# mini-store-selector.net
KiCad netlist of a schematic drawn in EAGLE
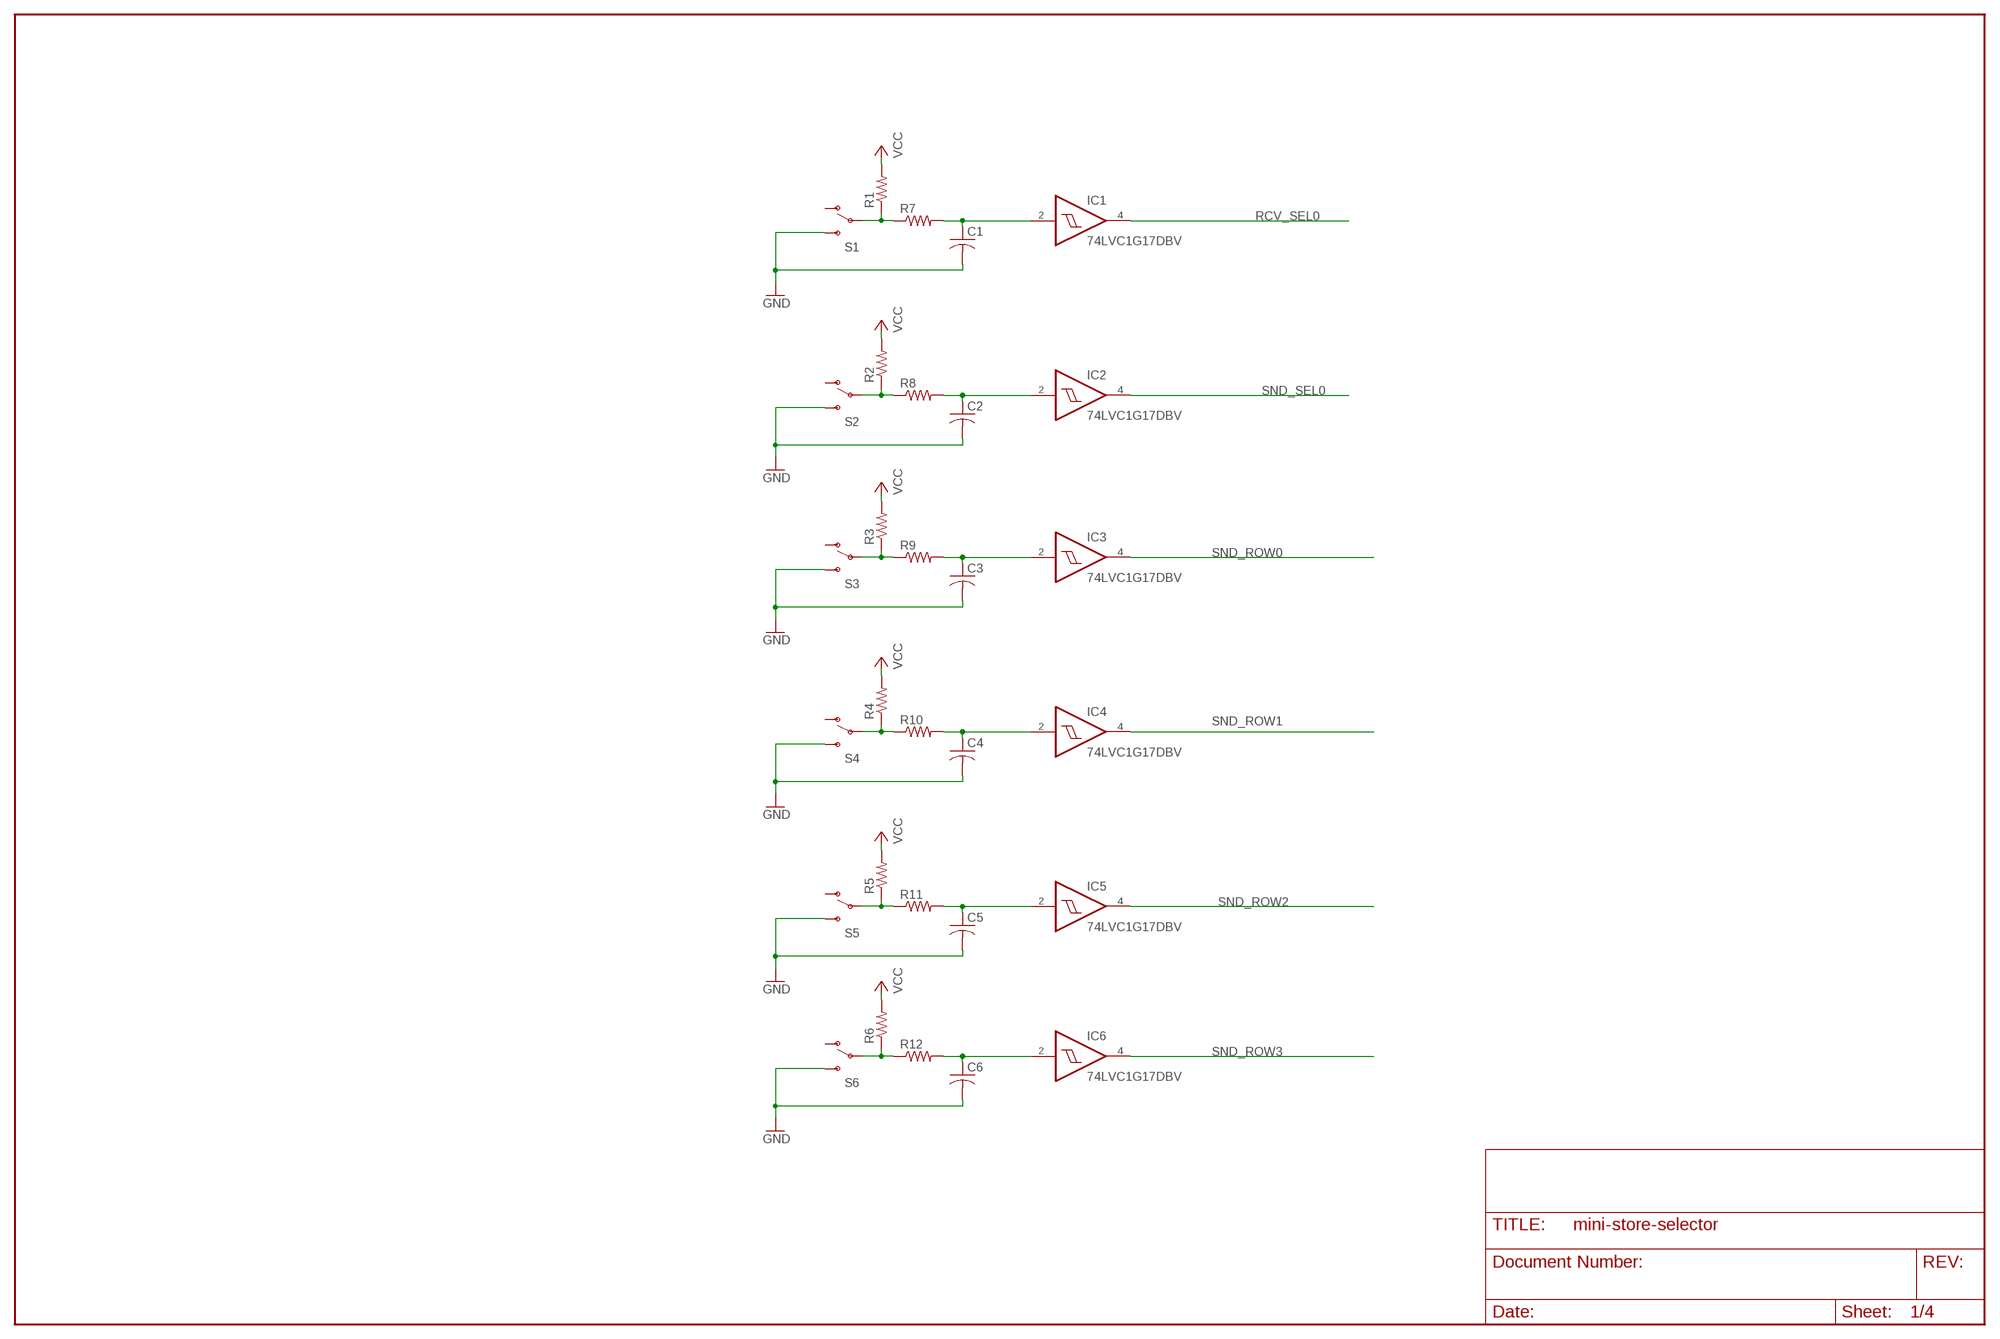
[diagram p0: schematic, sheet 1]
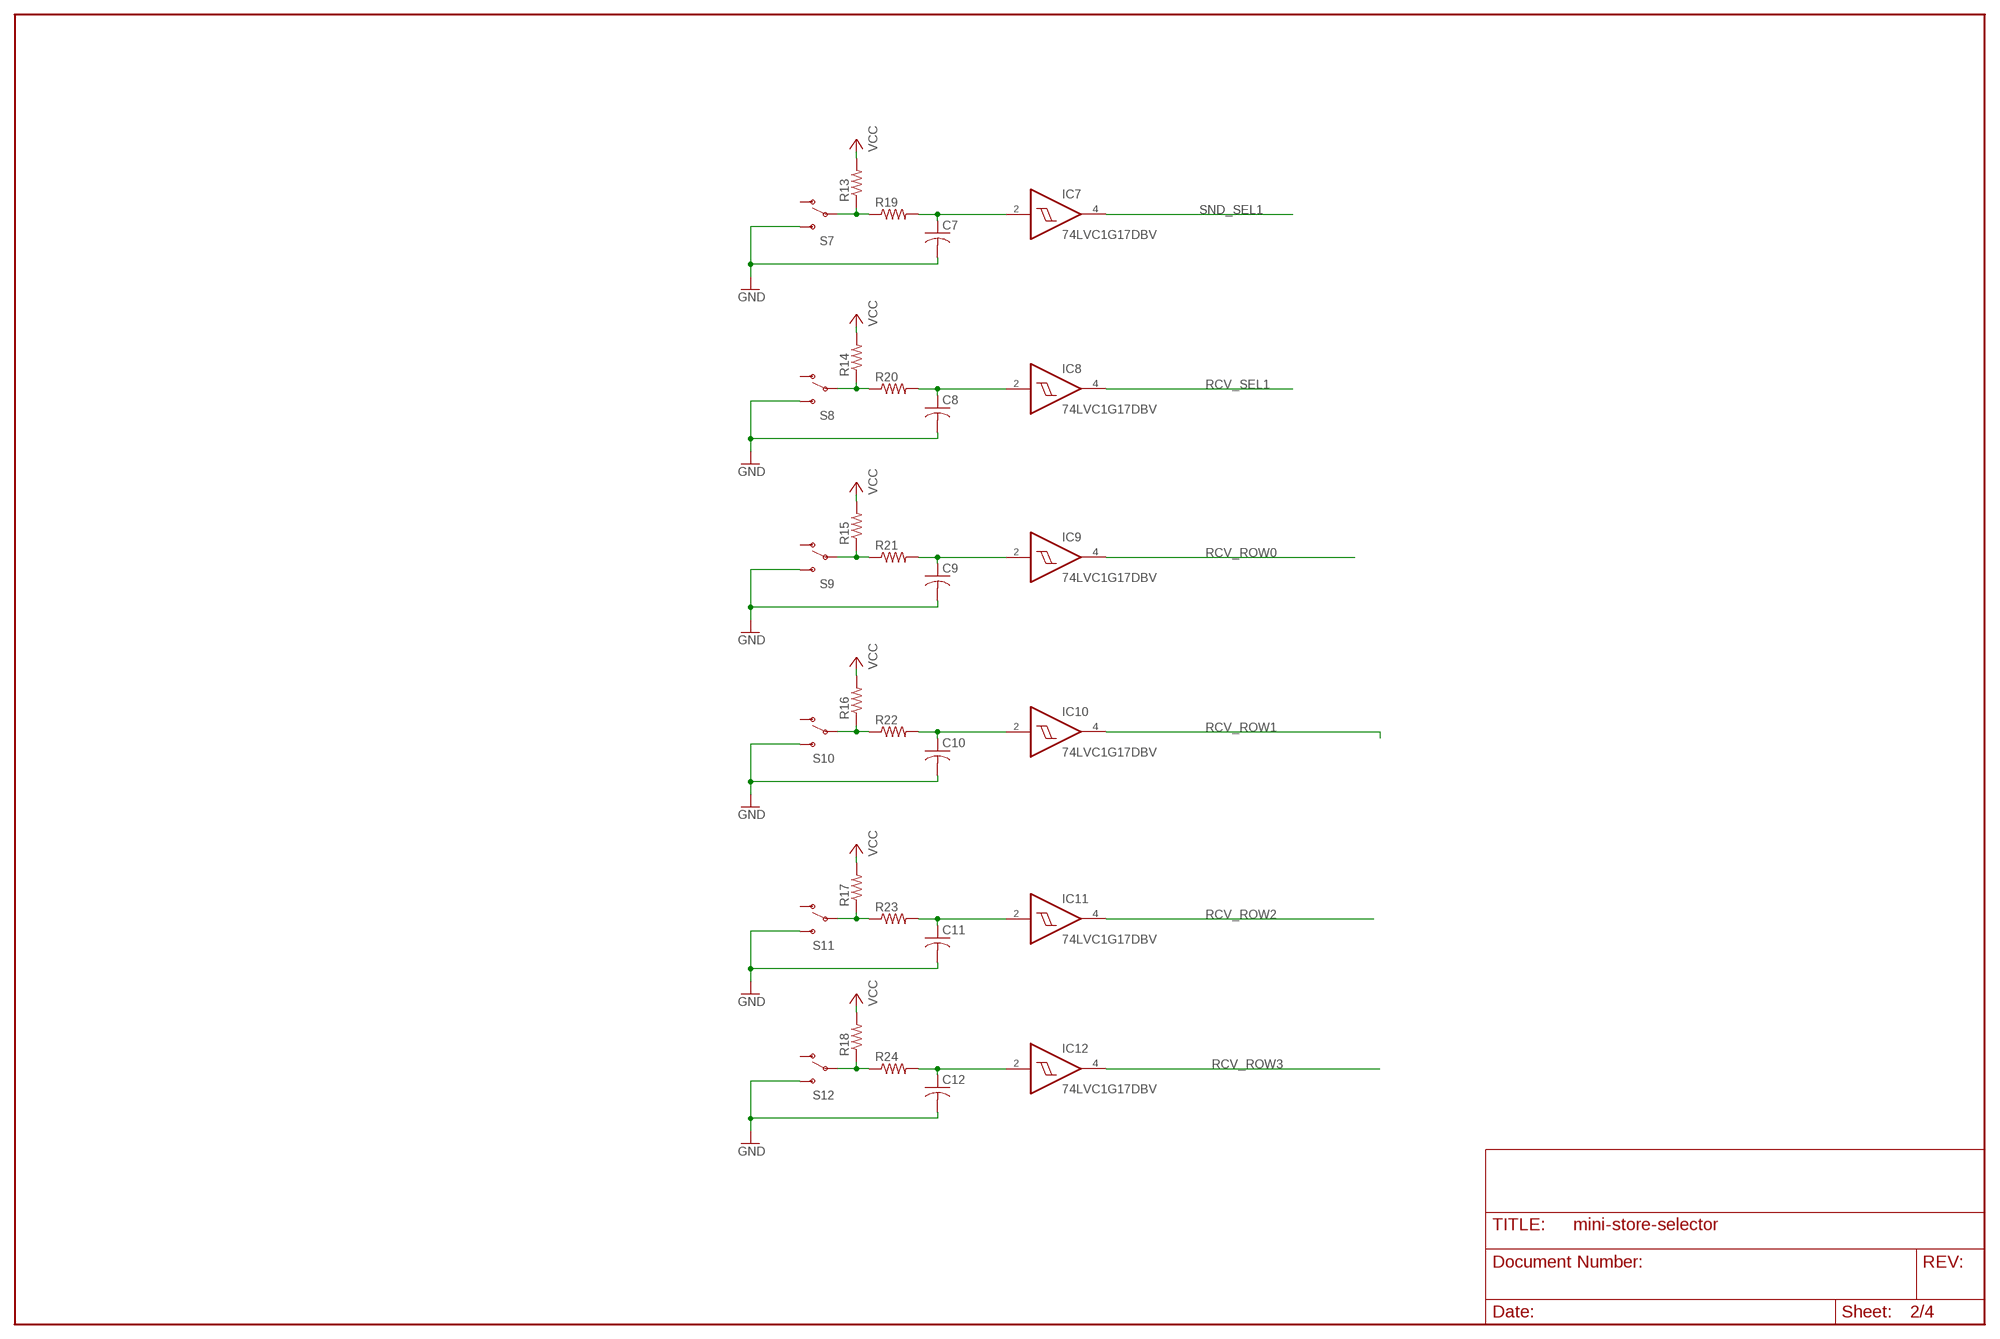
[diagram p1: schematic, sheet 2]
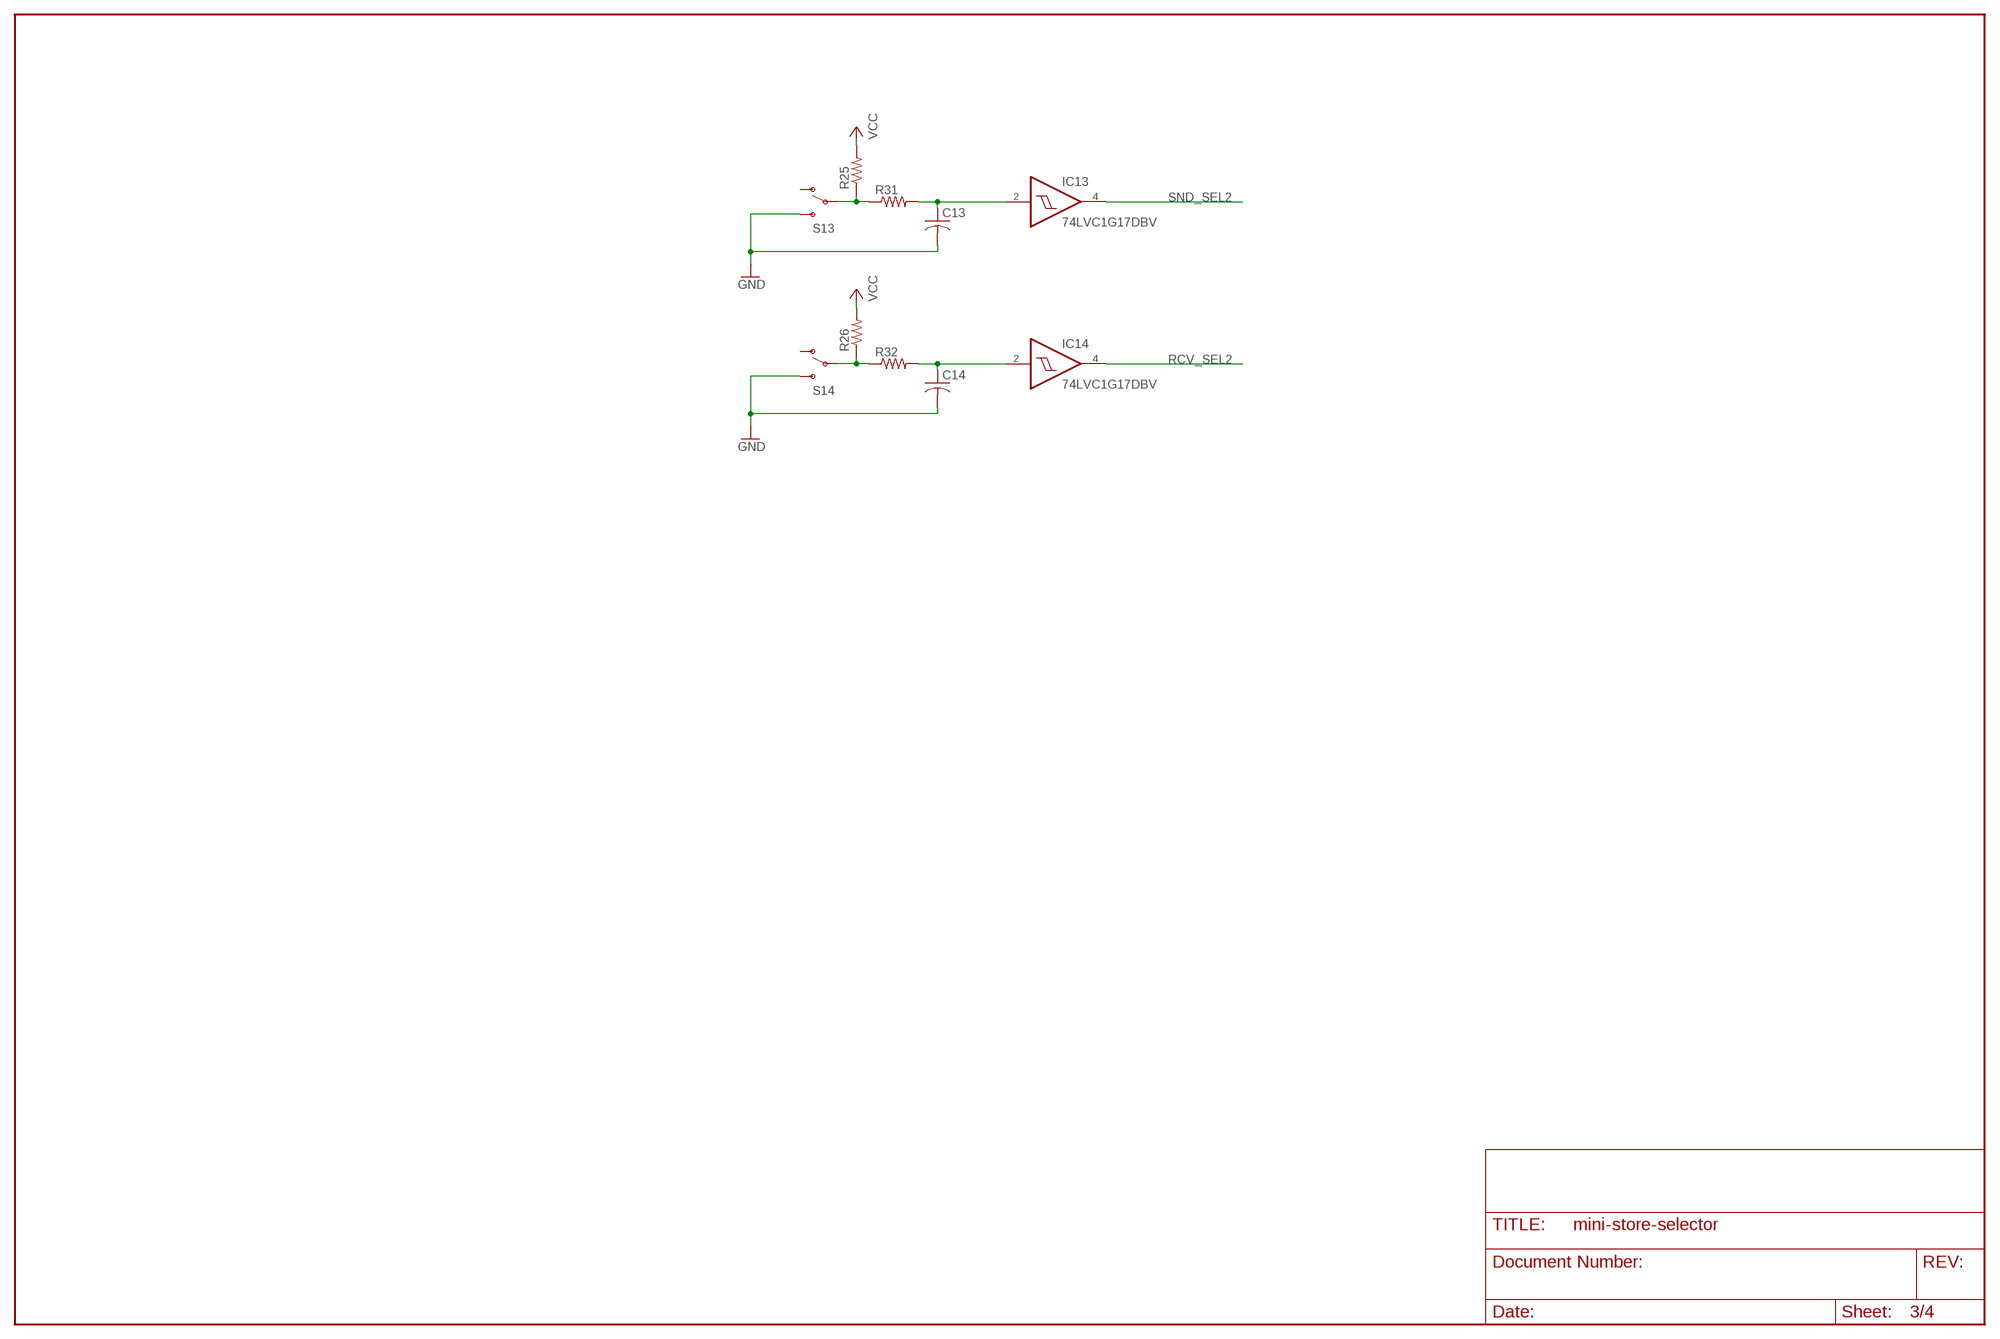
[diagram p2: schematic, sheet 3]
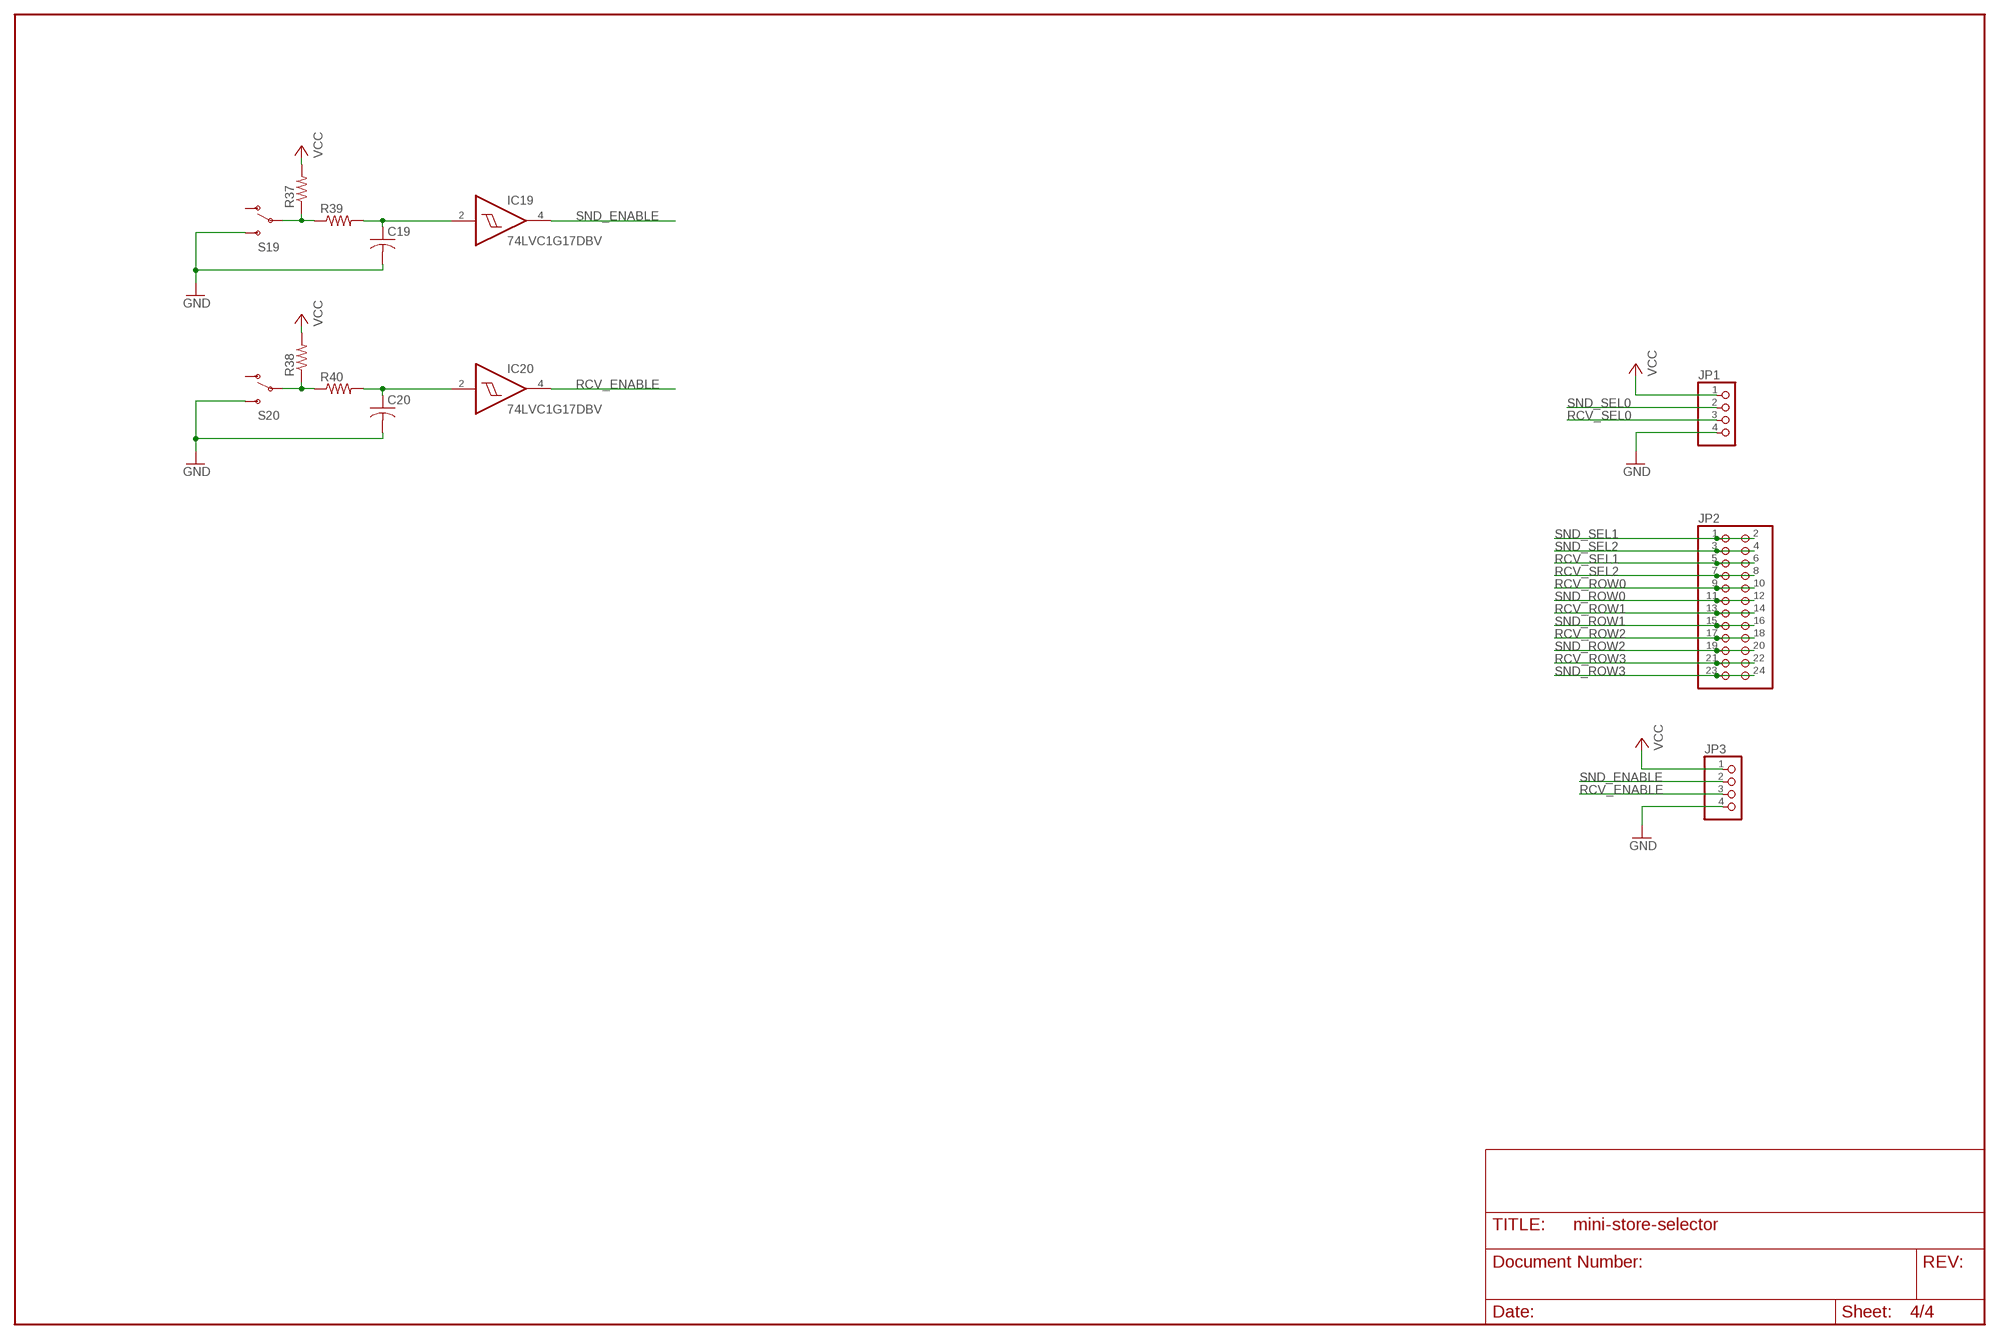
[diagram p3: schematic, sheet 4]

(export (version "E")
  (design (tool "Eeschema 10.0.6"))
  (components
    (comp (ref "C19")
      (value "C-USC0805")
      (footprint "eagle-import:C0805")
      (libsource (lib "eagle-import") (part "C-USC0805"))
    )
    (comp (ref "C20")
      (value "C-USC0805")
      (footprint "eagle-import:C0805")
      (libsource (lib "eagle-import") (part "C-USC0805"))
    )
    (comp (ref "IC19")
      (value "74LVC1G17DBV")
      (footprint "eagle-import:SOT23-5")
      (libsource (lib "eagle-import") (part "741G17DBVLVC"))
    )
    (comp (ref "IC20")
      (value "74LVC1G17DBV")
      (footprint "eagle-import:SOT23-5")
      (libsource (lib "eagle-import") (part "741G17DBVLVC"))
    )
    (comp (ref "JP1")
      (value "PINHD-1X4")
      (footprint "eagle-import:1X04")
      (libsource (lib "eagle-import") (part "PINHD-1X4"))
    )
    (comp (ref "JP2")
      (value "PINHD-2X12")
      (footprint "eagle-import:2X12")
      (libsource (lib "eagle-import") (part "PINHD-2X12"))
    )
    (comp (ref "JP3")
      (value "PINHD-1X4")
      (footprint "eagle-import:1X04")
      (libsource (lib "eagle-import") (part "PINHD-1X4"))
    )
    (comp (ref "R37")
      (value "R-US_R0805")
      (footprint "eagle-import:R0805")
      (libsource (lib "eagle-import") (part "R-US_R0805"))
    )
    (comp (ref "R38")
      (value "R-US_R0805")
      (footprint "eagle-import:R0805")
      (libsource (lib "eagle-import") (part "R-US_R0805"))
    )
    (comp (ref "R39")
      (value "R-US_R0805")
      (footprint "eagle-import:R0805")
      (libsource (lib "eagle-import") (part "R-US_R0805"))
    )
    (comp (ref "R40")
      (value "R-US_R0805")
      (footprint "eagle-import:R0805")
      (libsource (lib "eagle-import") (part "R-US_R0805"))
    )
    (comp (ref "S19")
      (value "SWITCH-SPDTPTH")
      (footprint "eagle-import:SWITCH-SPDT")
      (libsource (lib "eagle-import") (part "SWITCH-SPDTPTH"))
    )
    (comp (ref "S20")
      (value "SWITCH-SPDTPTH")
      (footprint "eagle-import:SWITCH-SPDT")
      (libsource (lib "eagle-import") (part "SWITCH-SPDTPTH"))
    )
    (comp (ref "C7")
      (value "C-USC0805")
      (footprint "eagle-import:C0805")
      (libsource (lib "eagle-import") (part "C-USC0805"))
    )
    (comp (ref "C8")
      (value "C-USC0805")
      (footprint "eagle-import:C0805")
      (libsource (lib "eagle-import") (part "C-USC0805"))
    )
    (comp (ref "C9")
      (value "C-USC0805")
      (footprint "eagle-import:C0805")
      (libsource (lib "eagle-import") (part "C-USC0805"))
    )
    (comp (ref "C10")
      (value "C-USC0805")
      (footprint "eagle-import:C0805")
      (libsource (lib "eagle-import") (part "C-USC0805"))
    )
    (comp (ref "C11")
      (value "C-USC0805")
      (footprint "eagle-import:C0805")
      (libsource (lib "eagle-import") (part "C-USC0805"))
    )
    (comp (ref "C12")
      (value "C-USC0805")
      (footprint "eagle-import:C0805")
      (libsource (lib "eagle-import") (part "C-USC0805"))
    )
    (comp (ref "IC7")
      (value "74LVC1G17DBV")
      (footprint "eagle-import:SOT23-5")
      (libsource (lib "eagle-import") (part "741G17DBVLVC"))
    )
    (comp (ref "IC8")
      (value "74LVC1G17DBV")
      (footprint "eagle-import:SOT23-5")
      (libsource (lib "eagle-import") (part "741G17DBVLVC"))
    )
    (comp (ref "IC9")
      (value "74LVC1G17DBV")
      (footprint "eagle-import:SOT23-5")
      (libsource (lib "eagle-import") (part "741G17DBVLVC"))
    )
    (comp (ref "IC10")
      (value "74LVC1G17DBV")
      (footprint "eagle-import:SOT23-5")
      (libsource (lib "eagle-import") (part "741G17DBVLVC"))
    )
    (comp (ref "IC11")
      (value "74LVC1G17DBV")
      (footprint "eagle-import:SOT23-5")
      (libsource (lib "eagle-import") (part "741G17DBVLVC"))
    )
    (comp (ref "IC12")
      (value "74LVC1G17DBV")
      (footprint "eagle-import:SOT23-5")
      (libsource (lib "eagle-import") (part "741G17DBVLVC"))
    )
    (comp (ref "R13")
      (value "R-US_R0805")
      (footprint "eagle-import:R0805")
      (libsource (lib "eagle-import") (part "R-US_R0805"))
    )
    (comp (ref "R14")
      (value "R-US_R0805")
      (footprint "eagle-import:R0805")
      (libsource (lib "eagle-import") (part "R-US_R0805"))
    )
    (comp (ref "R15")
      (value "R-US_R0805")
      (footprint "eagle-import:R0805")
      (libsource (lib "eagle-import") (part "R-US_R0805"))
    )
    (comp (ref "R16")
      (value "R-US_R0805")
      (footprint "eagle-import:R0805")
      (libsource (lib "eagle-import") (part "R-US_R0805"))
    )
    (comp (ref "R17")
      (value "R-US_R0805")
      (footprint "eagle-import:R0805")
      (libsource (lib "eagle-import") (part "R-US_R0805"))
    )
    (comp (ref "R18")
      (value "R-US_R0805")
      (footprint "eagle-import:R0805")
      (libsource (lib "eagle-import") (part "R-US_R0805"))
    )
    (comp (ref "R19")
      (value "R-US_R0805")
      (footprint "eagle-import:R0805")
      (libsource (lib "eagle-import") (part "R-US_R0805"))
    )
    (comp (ref "R20")
      (value "R-US_R0805")
      (footprint "eagle-import:R0805")
      (libsource (lib "eagle-import") (part "R-US_R0805"))
    )
    (comp (ref "R21")
      (value "R-US_R0805")
      (footprint "eagle-import:R0805")
      (libsource (lib "eagle-import") (part "R-US_R0805"))
    )
    (comp (ref "R22")
      (value "R-US_R0805")
      (footprint "eagle-import:R0805")
      (libsource (lib "eagle-import") (part "R-US_R0805"))
    )
    (comp (ref "R23")
      (value "R-US_R0805")
      (footprint "eagle-import:R0805")
      (libsource (lib "eagle-import") (part "R-US_R0805"))
    )
    (comp (ref "R24")
      (value "R-US_R0805")
      (footprint "eagle-import:R0805")
      (libsource (lib "eagle-import") (part "R-US_R0805"))
    )
    (comp (ref "S7")
      (value "SWITCH-SPDTPTH")
      (footprint "eagle-import:SWITCH-SPDT")
      (libsource (lib "eagle-import") (part "SWITCH-SPDTPTH"))
    )
    (comp (ref "S8")
      (value "SWITCH-SPDTPTH")
      (footprint "eagle-import:SWITCH-SPDT")
      (libsource (lib "eagle-import") (part "SWITCH-SPDTPTH"))
    )
    (comp (ref "S9")
      (value "SWITCH-SPDTPTH")
      (footprint "eagle-import:SWITCH-SPDT")
      (libsource (lib "eagle-import") (part "SWITCH-SPDTPTH"))
    )
    (comp (ref "S10")
      (value "SWITCH-SPDTPTH")
      (footprint "eagle-import:SWITCH-SPDT")
      (libsource (lib "eagle-import") (part "SWITCH-SPDTPTH"))
    )
    (comp (ref "S11")
      (value "SWITCH-SPDTPTH")
      (footprint "eagle-import:SWITCH-SPDT")
      (libsource (lib "eagle-import") (part "SWITCH-SPDTPTH"))
    )
    (comp (ref "S12")
      (value "SWITCH-SPDTPTH")
      (footprint "eagle-import:SWITCH-SPDT")
      (libsource (lib "eagle-import") (part "SWITCH-SPDTPTH"))
    )
    (comp (ref "C1")
      (value "C-USC0805")
      (footprint "eagle-import:C0805")
      (libsource (lib "eagle-import") (part "C-USC0805"))
    )
    (comp (ref "C2")
      (value "C-USC0805")
      (footprint "eagle-import:C0805")
      (libsource (lib "eagle-import") (part "C-USC0805"))
    )
    (comp (ref "C3")
      (value "C-USC0805")
      (footprint "eagle-import:C0805")
      (libsource (lib "eagle-import") (part "C-USC0805"))
    )
    (comp (ref "C4")
      (value "C-USC0805")
      (footprint "eagle-import:C0805")
      (libsource (lib "eagle-import") (part "C-USC0805"))
    )
    (comp (ref "C5")
      (value "C-USC0805")
      (footprint "eagle-import:C0805")
      (libsource (lib "eagle-import") (part "C-USC0805"))
    )
    (comp (ref "C6")
      (value "C-USC0805")
      (footprint "eagle-import:C0805")
      (libsource (lib "eagle-import") (part "C-USC0805"))
    )
    (comp (ref "IC1")
      (value "74LVC1G17DBV")
      (footprint "eagle-import:SOT23-5")
      (libsource (lib "eagle-import") (part "741G17DBVLVC"))
    )
    (comp (ref "IC2")
      (value "74LVC1G17DBV")
      (footprint "eagle-import:SOT23-5")
      (libsource (lib "eagle-import") (part "741G17DBVLVC"))
    )
    (comp (ref "IC3")
      (value "74LVC1G17DBV")
      (footprint "eagle-import:SOT23-5")
      (libsource (lib "eagle-import") (part "741G17DBVLVC"))
    )
    (comp (ref "IC4")
      (value "74LVC1G17DBV")
      (footprint "eagle-import:SOT23-5")
      (libsource (lib "eagle-import") (part "741G17DBVLVC"))
    )
    (comp (ref "IC5")
      (value "74LVC1G17DBV")
      (footprint "eagle-import:SOT23-5")
      (libsource (lib "eagle-import") (part "741G17DBVLVC"))
    )
    (comp (ref "IC6")
      (value "74LVC1G17DBV")
      (footprint "eagle-import:SOT23-5")
      (libsource (lib "eagle-import") (part "741G17DBVLVC"))
    )
    (comp (ref "R1")
      (value "R-US_R0805")
      (footprint "eagle-import:R0805")
      (libsource (lib "eagle-import") (part "R-US_R0805"))
    )
    (comp (ref "R2")
      (value "R-US_R0805")
      (footprint "eagle-import:R0805")
      (libsource (lib "eagle-import") (part "R-US_R0805"))
    )
    (comp (ref "R3")
      (value "R-US_R0805")
      (footprint "eagle-import:R0805")
      (libsource (lib "eagle-import") (part "R-US_R0805"))
    )
    (comp (ref "R4")
      (value "R-US_R0805")
      (footprint "eagle-import:R0805")
      (libsource (lib "eagle-import") (part "R-US_R0805"))
    )
    (comp (ref "R5")
      (value "R-US_R0805")
      (footprint "eagle-import:R0805")
      (libsource (lib "eagle-import") (part "R-US_R0805"))
    )
    (comp (ref "R6")
      (value "R-US_R0805")
      (footprint "eagle-import:R0805")
      (libsource (lib "eagle-import") (part "R-US_R0805"))
    )
    (comp (ref "R7")
      (value "R-US_R0805")
      (footprint "eagle-import:R0805")
      (libsource (lib "eagle-import") (part "R-US_R0805"))
    )
    (comp (ref "R8")
      (value "R-US_R0805")
      (footprint "eagle-import:R0805")
      (libsource (lib "eagle-import") (part "R-US_R0805"))
    )
    (comp (ref "R9")
      (value "R-US_R0805")
      (footprint "eagle-import:R0805")
      (libsource (lib "eagle-import") (part "R-US_R0805"))
    )
    (comp (ref "R10")
      (value "R-US_R0805")
      (footprint "eagle-import:R0805")
      (libsource (lib "eagle-import") (part "R-US_R0805"))
    )
    (comp (ref "R11")
      (value "R-US_R0805")
      (footprint "eagle-import:R0805")
      (libsource (lib "eagle-import") (part "R-US_R0805"))
    )
    (comp (ref "R12")
      (value "R-US_R0805")
      (footprint "eagle-import:R0805")
      (libsource (lib "eagle-import") (part "R-US_R0805"))
    )
    (comp (ref "S1")
      (value "SWITCH-SPDTPTH")
      (footprint "eagle-import:SWITCH-SPDT")
      (libsource (lib "eagle-import") (part "SWITCH-SPDTPTH"))
    )
    (comp (ref "S2")
      (value "SWITCH-SPDTPTH")
      (footprint "eagle-import:SWITCH-SPDT")
      (libsource (lib "eagle-import") (part "SWITCH-SPDTPTH"))
    )
    (comp (ref "S3")
      (value "SWITCH-SPDTPTH")
      (footprint "eagle-import:SWITCH-SPDT")
      (libsource (lib "eagle-import") (part "SWITCH-SPDTPTH"))
    )
    (comp (ref "S4")
      (value "SWITCH-SPDTPTH")
      (footprint "eagle-import:SWITCH-SPDT")
      (libsource (lib "eagle-import") (part "SWITCH-SPDTPTH"))
    )
    (comp (ref "S5")
      (value "SWITCH-SPDTPTH")
      (footprint "eagle-import:SWITCH-SPDT")
      (libsource (lib "eagle-import") (part "SWITCH-SPDTPTH"))
    )
    (comp (ref "S6")
      (value "SWITCH-SPDTPTH")
      (footprint "eagle-import:SWITCH-SPDT")
      (libsource (lib "eagle-import") (part "SWITCH-SPDTPTH"))
    )
    (comp (ref "C13")
      (value "C-USC0805")
      (footprint "eagle-import:C0805")
      (libsource (lib "eagle-import") (part "C-USC0805"))
    )
    (comp (ref "C14")
      (value "C-USC0805")
      (footprint "eagle-import:C0805")
      (libsource (lib "eagle-import") (part "C-USC0805"))
    )
    (comp (ref "IC13")
      (value "74LVC1G17DBV")
      (footprint "eagle-import:SOT23-5")
      (libsource (lib "eagle-import") (part "741G17DBVLVC"))
    )
    (comp (ref "IC14")
      (value "74LVC1G17DBV")
      (footprint "eagle-import:SOT23-5")
      (libsource (lib "eagle-import") (part "741G17DBVLVC"))
    )
    (comp (ref "R25")
      (value "R-US_R0805")
      (footprint "eagle-import:R0805")
      (libsource (lib "eagle-import") (part "R-US_R0805"))
    )
    (comp (ref "R26")
      (value "R-US_R0805")
      (footprint "eagle-import:R0805")
      (libsource (lib "eagle-import") (part "R-US_R0805"))
    )
    (comp (ref "R31")
      (value "R-US_R0805")
      (footprint "eagle-import:R0805")
      (libsource (lib "eagle-import") (part "R-US_R0805"))
    )
    (comp (ref "R32")
      (value "R-US_R0805")
      (footprint "eagle-import:R0805")
      (libsource (lib "eagle-import") (part "R-US_R0805"))
    )
    (comp (ref "S13")
      (value "SWITCH-SPDTPTH")
      (footprint "eagle-import:SWITCH-SPDT")
      (libsource (lib "eagle-import") (part "SWITCH-SPDTPTH"))
    )
    (comp (ref "S14")
      (value "SWITCH-SPDTPTH")
      (footprint "eagle-import:SWITCH-SPDT")
      (libsource (lib "eagle-import") (part "SWITCH-SPDTPTH"))
    )
  )
  (nets
    (net (code "1") (name "GND") (class "Default")
      (node (ref "C1") (pin "2") (pinfunction "2_2") (pintype "passive"))
      (node (ref "C10") (pin "2") (pinfunction "2_2") (pintype "passive"))
      (node (ref "C11") (pin "2") (pinfunction "2_2") (pintype "passive"))
      (node (ref "C12") (pin "2") (pinfunction "2_2") (pintype "passive"))
      (node (ref "C13") (pin "2") (pinfunction "2_2") (pintype "passive"))
      (node (ref "C14") (pin "2") (pinfunction "2_2") (pintype "passive"))
      (node (ref "C19") (pin "2") (pinfunction "2_2") (pintype "passive"))
      (node (ref "C2") (pin "2") (pinfunction "2_2") (pintype "passive"))
      (node (ref "C20") (pin "2") (pinfunction "2_2") (pintype "passive"))
      (node (ref "C3") (pin "2") (pinfunction "2_2") (pintype "passive"))
      (node (ref "C4") (pin "2") (pinfunction "2_2") (pintype "passive"))
      (node (ref "C5") (pin "2") (pinfunction "2_2") (pintype "passive"))
      (node (ref "C6") (pin "2") (pinfunction "2_2") (pintype "passive"))
      (node (ref "C7") (pin "2") (pinfunction "2_2") (pintype "passive"))
      (node (ref "C8") (pin "2") (pinfunction "2_2") (pintype "passive"))
      (node (ref "C9") (pin "2") (pinfunction "2_2") (pintype "passive"))
      (node (ref "JP1") (pin "4") (pinfunction "4_4") (pintype "passive"))
      (node (ref "JP3") (pin "4") (pinfunction "4_4") (pintype "passive"))
      (node (ref "S1") (pin "3") (pinfunction "S_3") (pintype "passive"))
      (node (ref "S10") (pin "3") (pinfunction "S_3") (pintype "passive"))
      (node (ref "S11") (pin "3") (pinfunction "S_3") (pintype "passive"))
      (node (ref "S12") (pin "3") (pinfunction "S_3") (pintype "passive"))
      (node (ref "S13") (pin "3") (pinfunction "S_3") (pintype "passive"))
      (node (ref "S14") (pin "3") (pinfunction "S_3") (pintype "passive"))
      (node (ref "S19") (pin "3") (pinfunction "S_3") (pintype "passive"))
      (node (ref "S2") (pin "3") (pinfunction "S_3") (pintype "passive"))
      (node (ref "S20") (pin "3") (pinfunction "S_3") (pintype "passive"))
      (node (ref "S3") (pin "3") (pinfunction "S_3") (pintype "passive"))
      (node (ref "S4") (pin "3") (pinfunction "S_3") (pintype "passive"))
      (node (ref "S5") (pin "3") (pinfunction "S_3") (pintype "passive"))
      (node (ref "S6") (pin "3") (pinfunction "S_3") (pintype "passive"))
      (node (ref "S7") (pin "3") (pinfunction "S_3") (pintype "passive"))
      (node (ref "S8") (pin "3") (pinfunction "S_3") (pintype "passive"))
      (node (ref "S9") (pin "3") (pinfunction "S_3") (pintype "passive"))
    )
    (net (code "2") (name "Net-(IC1A-I)") (class "Default")
      (node (ref "C1") (pin "1") (pinfunction "1_1") (pintype "passive"))
      (node (ref "IC1") (pin "2") (pinfunction "I_2") (pintype "input"))
      (node (ref "R7") (pin "2") (pinfunction "2_2") (pintype "passive"))
    )
    (net (code "3") (name "Net-(IC2A-I)") (class "Default")
      (node (ref "C2") (pin "1") (pinfunction "1_1") (pintype "passive"))
      (node (ref "IC2") (pin "2") (pinfunction "I_2") (pintype "input"))
      (node (ref "R8") (pin "2") (pinfunction "2_2") (pintype "passive"))
    )
    (net (code "4") (name "Net-(IC3A-I)") (class "Default")
      (node (ref "C3") (pin "1") (pinfunction "1_1") (pintype "passive"))
      (node (ref "IC3") (pin "2") (pinfunction "I_2") (pintype "input"))
      (node (ref "R9") (pin "2") (pinfunction "2_2") (pintype "passive"))
    )
    (net (code "5") (name "Net-(IC4A-I)") (class "Default")
      (node (ref "C4") (pin "1") (pinfunction "1_1") (pintype "passive"))
      (node (ref "IC4") (pin "2") (pinfunction "I_2") (pintype "input"))
      (node (ref "R10") (pin "2") (pinfunction "2_2") (pintype "passive"))
    )
    (net (code "6") (name "Net-(IC5A-I)") (class "Default")
      (node (ref "C5") (pin "1") (pinfunction "1_1") (pintype "passive"))
      (node (ref "IC5") (pin "2") (pinfunction "I_2") (pintype "input"))
      (node (ref "R11") (pin "2") (pinfunction "2_2") (pintype "passive"))
    )
    (net (code "7") (name "Net-(IC6A-I)") (class "Default")
      (node (ref "C6") (pin "1") (pinfunction "1_1") (pintype "passive"))
      (node (ref "IC6") (pin "2") (pinfunction "I_2") (pintype "input"))
      (node (ref "R12") (pin "2") (pinfunction "2_2") (pintype "passive"))
    )
    (net (code "8") (name "Net-(IC7A-I)") (class "Default")
      (node (ref "C7") (pin "1") (pinfunction "1_1") (pintype "passive"))
      (node (ref "IC7") (pin "2") (pinfunction "I_2") (pintype "input"))
      (node (ref "R19") (pin "2") (pinfunction "2_2") (pintype "passive"))
    )
    (net (code "9") (name "Net-(IC8A-I)") (class "Default")
      (node (ref "C8") (pin "1") (pinfunction "1_1") (pintype "passive"))
      (node (ref "IC8") (pin "2") (pinfunction "I_2") (pintype "input"))
      (node (ref "R20") (pin "2") (pinfunction "2_2") (pintype "passive"))
    )
    (net (code "10") (name "Net-(IC9A-I)") (class "Default")
      (node (ref "C9") (pin "1") (pinfunction "1_1") (pintype "passive"))
      (node (ref "IC9") (pin "2") (pinfunction "I_2") (pintype "input"))
      (node (ref "R21") (pin "2") (pinfunction "2_2") (pintype "passive"))
    )
    (net (code "11") (name "Net-(IC10A-I)") (class "Default")
      (node (ref "C10") (pin "1") (pinfunction "1_1") (pintype "passive"))
      (node (ref "IC10") (pin "2") (pinfunction "I_2") (pintype "input"))
      (node (ref "R22") (pin "2") (pinfunction "2_2") (pintype "passive"))
    )
    (net (code "12") (name "Net-(IC11A-I)") (class "Default")
      (node (ref "C11") (pin "1") (pinfunction "1_1") (pintype "passive"))
      (node (ref "IC11") (pin "2") (pinfunction "I_2") (pintype "input"))
      (node (ref "R23") (pin "2") (pinfunction "2_2") (pintype "passive"))
    )
    (net (code "13") (name "Net-(IC12A-I)") (class "Default")
      (node (ref "C12") (pin "1") (pinfunction "1_1") (pintype "passive"))
      (node (ref "IC12") (pin "2") (pinfunction "I_2") (pintype "input"))
      (node (ref "R24") (pin "2") (pinfunction "2_2") (pintype "passive"))
    )
    (net (code "14") (name "Net-(IC13A-I)") (class "Default")
      (node (ref "C13") (pin "1") (pinfunction "1_1") (pintype "passive"))
      (node (ref "IC13") (pin "2") (pinfunction "I_2") (pintype "input"))
      (node (ref "R31") (pin "2") (pinfunction "2_2") (pintype "passive"))
    )
    (net (code "15") (name "Net-(IC14A-I)") (class "Default")
      (node (ref "C14") (pin "1") (pinfunction "1_1") (pintype "passive"))
      (node (ref "IC14") (pin "2") (pinfunction "I_2") (pintype "input"))
      (node (ref "R32") (pin "2") (pinfunction "2_2") (pintype "passive"))
    )
    (net (code "16") (name "Net-(IC19A-I)") (class "Default")
      (node (ref "C19") (pin "1") (pinfunction "1_1") (pintype "passive"))
      (node (ref "IC19") (pin "2") (pinfunction "I_2") (pintype "input"))
      (node (ref "R39") (pin "2") (pinfunction "2_2") (pintype "passive"))
    )
    (net (code "17") (name "Net-(IC20A-I)") (class "Default")
      (node (ref "C20") (pin "1") (pinfunction "1_1") (pintype "passive"))
      (node (ref "IC20") (pin "2") (pinfunction "I_2") (pintype "input"))
      (node (ref "R40") (pin "2") (pinfunction "2_2") (pintype "passive"))
    )
    (net (code "18") (name "Net-(S1-P)") (class "Default")
      (node (ref "R1") (pin "1") (pinfunction "1_1") (pintype "passive"))
      (node (ref "R7") (pin "1") (pinfunction "1_1") (pintype "passive"))
      (node (ref "S1") (pin "2") (pinfunction "P_2") (pintype "passive"))
    )
    (net (code "19") (name "Net-(S2-P)") (class "Default")
      (node (ref "R2") (pin "1") (pinfunction "1_1") (pintype "passive"))
      (node (ref "R8") (pin "1") (pinfunction "1_1") (pintype "passive"))
      (node (ref "S2") (pin "2") (pinfunction "P_2") (pintype "passive"))
    )
    (net (code "20") (name "Net-(S3-P)") (class "Default")
      (node (ref "R3") (pin "1") (pinfunction "1_1") (pintype "passive"))
      (node (ref "R9") (pin "1") (pinfunction "1_1") (pintype "passive"))
      (node (ref "S3") (pin "2") (pinfunction "P_2") (pintype "passive"))
    )
    (net (code "21") (name "Net-(S4-P)") (class "Default")
      (node (ref "R10") (pin "1") (pinfunction "1_1") (pintype "passive"))
      (node (ref "R4") (pin "1") (pinfunction "1_1") (pintype "passive"))
      (node (ref "S4") (pin "2") (pinfunction "P_2") (pintype "passive"))
    )
    (net (code "22") (name "Net-(S5-P)") (class "Default")
      (node (ref "R11") (pin "1") (pinfunction "1_1") (pintype "passive"))
      (node (ref "R5") (pin "1") (pinfunction "1_1") (pintype "passive"))
      (node (ref "S5") (pin "2") (pinfunction "P_2") (pintype "passive"))
    )
    (net (code "23") (name "Net-(S6-P)") (class "Default")
      (node (ref "R12") (pin "1") (pinfunction "1_1") (pintype "passive"))
      (node (ref "R6") (pin "1") (pinfunction "1_1") (pintype "passive"))
      (node (ref "S6") (pin "2") (pinfunction "P_2") (pintype "passive"))
    )
    (net (code "24") (name "Net-(S7-P)") (class "Default")
      (node (ref "R13") (pin "1") (pinfunction "1_1") (pintype "passive"))
      (node (ref "R19") (pin "1") (pinfunction "1_1") (pintype "passive"))
      (node (ref "S7") (pin "2") (pinfunction "P_2") (pintype "passive"))
    )
    (net (code "25") (name "Net-(S8-P)") (class "Default")
      (node (ref "R14") (pin "1") (pinfunction "1_1") (pintype "passive"))
      (node (ref "R20") (pin "1") (pinfunction "1_1") (pintype "passive"))
      (node (ref "S8") (pin "2") (pinfunction "P_2") (pintype "passive"))
    )
    (net (code "26") (name "Net-(S9-P)") (class "Default")
      (node (ref "R15") (pin "1") (pinfunction "1_1") (pintype "passive"))
      (node (ref "R21") (pin "1") (pinfunction "1_1") (pintype "passive"))
      (node (ref "S9") (pin "2") (pinfunction "P_2") (pintype "passive"))
    )
    (net (code "27") (name "Net-(S10-P)") (class "Default")
      (node (ref "R16") (pin "1") (pinfunction "1_1") (pintype "passive"))
      (node (ref "R22") (pin "1") (pinfunction "1_1") (pintype "passive"))
      (node (ref "S10") (pin "2") (pinfunction "P_2") (pintype "passive"))
    )
    (net (code "28") (name "Net-(S11-P)") (class "Default")
      (node (ref "R17") (pin "1") (pinfunction "1_1") (pintype "passive"))
      (node (ref "R23") (pin "1") (pinfunction "1_1") (pintype "passive"))
      (node (ref "S11") (pin "2") (pinfunction "P_2") (pintype "passive"))
    )
    (net (code "29") (name "Net-(S12-P)") (class "Default")
      (node (ref "R18") (pin "1") (pinfunction "1_1") (pintype "passive"))
      (node (ref "R24") (pin "1") (pinfunction "1_1") (pintype "passive"))
      (node (ref "S12") (pin "2") (pinfunction "P_2") (pintype "passive"))
    )
    (net (code "30") (name "Net-(S13-P)") (class "Default")
      (node (ref "R25") (pin "1") (pinfunction "1_1") (pintype "passive"))
      (node (ref "R31") (pin "1") (pinfunction "1_1") (pintype "passive"))
      (node (ref "S13") (pin "2") (pinfunction "P_2") (pintype "passive"))
    )
    (net (code "31") (name "Net-(S14-P)") (class "Default")
      (node (ref "R26") (pin "1") (pinfunction "1_1") (pintype "passive"))
      (node (ref "R32") (pin "1") (pinfunction "1_1") (pintype "passive"))
      (node (ref "S14") (pin "2") (pinfunction "P_2") (pintype "passive"))
    )
    (net (code "32") (name "Net-(S19-P)") (class "Default")
      (node (ref "R37") (pin "1") (pinfunction "1_1") (pintype "passive"))
      (node (ref "R39") (pin "1") (pinfunction "1_1") (pintype "passive"))
      (node (ref "S19") (pin "2") (pinfunction "P_2") (pintype "passive"))
    )
    (net (code "33") (name "Net-(S20-P)") (class "Default")
      (node (ref "R38") (pin "1") (pinfunction "1_1") (pintype "passive"))
      (node (ref "R40") (pin "1") (pinfunction "1_1") (pintype "passive"))
      (node (ref "S20") (pin "2") (pinfunction "P_2") (pintype "passive"))
    )
    (net (code "34") (name "RCV_ENABLE") (class "Default")
      (node (ref "IC20") (pin "4") (pinfunction "O_4") (pintype "output"))
      (node (ref "JP3") (pin "3") (pinfunction "3_3") (pintype "passive"))
    )
    (net (code "35") (name "RCV_ROW0") (class "Default")
      (node (ref "IC9") (pin "4") (pinfunction "O_4") (pintype "output"))
      (node (ref "JP2") (pin "10") (pinfunction "10_10") (pintype "passive"))
      (node (ref "JP2") (pin "9") (pinfunction "9_9") (pintype "passive"))
    )
    (net (code "36") (name "RCV_ROW1") (class "Default")
      (node (ref "IC10") (pin "4") (pinfunction "O_4") (pintype "output"))
      (node (ref "JP2") (pin "13") (pinfunction "13_13") (pintype "passive"))
      (node (ref "JP2") (pin "14") (pinfunction "14_14") (pintype "passive"))
    )
    (net (code "37") (name "RCV_ROW2") (class "Default")
      (node (ref "IC11") (pin "4") (pinfunction "O_4") (pintype "output"))
      (node (ref "JP2") (pin "17") (pinfunction "17_17") (pintype "passive"))
      (node (ref "JP2") (pin "18") (pinfunction "18_18") (pintype "passive"))
    )
    (net (code "38") (name "RCV_ROW3") (class "Default")
      (node (ref "IC12") (pin "4") (pinfunction "O_4") (pintype "output"))
      (node (ref "JP2") (pin "21") (pinfunction "21_21") (pintype "passive"))
      (node (ref "JP2") (pin "22") (pinfunction "22_22") (pintype "passive"))
    )
    (net (code "39") (name "RCV_SEL0") (class "Default")
      (node (ref "IC1") (pin "4") (pinfunction "O_4") (pintype "output"))
      (node (ref "JP1") (pin "3") (pinfunction "3_3") (pintype "passive"))
    )
    (net (code "40") (name "RCV_SEL1") (class "Default")
      (node (ref "IC8") (pin "4") (pinfunction "O_4") (pintype "output"))
      (node (ref "JP2") (pin "5") (pinfunction "5_5") (pintype "passive"))
      (node (ref "JP2") (pin "6") (pinfunction "6_6") (pintype "passive"))
    )
    (net (code "41") (name "RCV_SEL2") (class "Default")
      (node (ref "IC14") (pin "4") (pinfunction "O_4") (pintype "output"))
      (node (ref "JP2") (pin "7") (pinfunction "7_7") (pintype "passive"))
      (node (ref "JP2") (pin "8") (pinfunction "8_8") (pintype "passive"))
    )
    (net (code "42") (name "SND_ENABLE") (class "Default")
      (node (ref "IC19") (pin "4") (pinfunction "O_4") (pintype "output"))
      (node (ref "JP3") (pin "2") (pinfunction "2_2") (pintype "passive"))
    )
    (net (code "43") (name "SND_ROW0") (class "Default")
      (node (ref "IC3") (pin "4") (pinfunction "O_4") (pintype "output"))
      (node (ref "JP2") (pin "11") (pinfunction "11_11") (pintype "passive"))
      (node (ref "JP2") (pin "12") (pinfunction "12_12") (pintype "passive"))
    )
    (net (code "44") (name "SND_ROW1") (class "Default")
      (node (ref "IC4") (pin "4") (pinfunction "O_4") (pintype "output"))
      (node (ref "JP2") (pin "15") (pinfunction "15_15") (pintype "passive"))
      (node (ref "JP2") (pin "16") (pinfunction "16_16") (pintype "passive"))
    )
    (net (code "45") (name "SND_ROW2") (class "Default")
      (node (ref "IC5") (pin "4") (pinfunction "O_4") (pintype "output"))
      (node (ref "JP2") (pin "19") (pinfunction "19_19") (pintype "passive"))
      (node (ref "JP2") (pin "20") (pinfunction "20_20") (pintype "passive"))
    )
    (net (code "46") (name "SND_ROW3") (class "Default")
      (node (ref "IC6") (pin "4") (pinfunction "O_4") (pintype "output"))
      (node (ref "JP2") (pin "23") (pinfunction "23_23") (pintype "passive"))
      (node (ref "JP2") (pin "24") (pinfunction "24_24") (pintype "passive"))
    )
    (net (code "47") (name "SND_SEL0") (class "Default")
      (node (ref "IC2") (pin "4") (pinfunction "O_4") (pintype "output"))
      (node (ref "JP1") (pin "2") (pinfunction "2_2") (pintype "passive"))
    )
    (net (code "48") (name "SND_SEL1") (class "Default")
      (node (ref "IC7") (pin "4") (pinfunction "O_4") (pintype "output"))
      (node (ref "JP2") (pin "1") (pinfunction "1_1") (pintype "passive"))
      (node (ref "JP2") (pin "2") (pinfunction "2_2") (pintype "passive"))
    )
    (net (code "49") (name "SND_SEL2") (class "Default")
      (node (ref "IC13") (pin "4") (pinfunction "O_4") (pintype "output"))
      (node (ref "JP2") (pin "3") (pinfunction "3_3") (pintype "passive"))
      (node (ref "JP2") (pin "4") (pinfunction "4_4") (pintype "passive"))
    )
    (net (code "50") (name "VCC") (class "Default")
      (node (ref "JP1") (pin "1") (pinfunction "1_1") (pintype "passive"))
      (node (ref "JP3") (pin "1") (pinfunction "1_1") (pintype "passive"))
      (node (ref "R1") (pin "2") (pinfunction "2_2") (pintype "passive"))
      (node (ref "R13") (pin "2") (pinfunction "2_2") (pintype "passive"))
      (node (ref "R14") (pin "2") (pinfunction "2_2") (pintype "passive"))
      (node (ref "R15") (pin "2") (pinfunction "2_2") (pintype "passive"))
      (node (ref "R16") (pin "2") (pinfunction "2_2") (pintype "passive"))
      (node (ref "R17") (pin "2") (pinfunction "2_2") (pintype "passive"))
      (node (ref "R18") (pin "2") (pinfunction "2_2") (pintype "passive"))
      (node (ref "R2") (pin "2") (pinfunction "2_2") (pintype "passive"))
      (node (ref "R25") (pin "2") (pinfunction "2_2") (pintype "passive"))
      (node (ref "R26") (pin "2") (pinfunction "2_2") (pintype "passive"))
      (node (ref "R3") (pin "2") (pinfunction "2_2") (pintype "passive"))
      (node (ref "R37") (pin "2") (pinfunction "2_2") (pintype "passive"))
      (node (ref "R38") (pin "2") (pinfunction "2_2") (pintype "passive"))
      (node (ref "R4") (pin "2") (pinfunction "2_2") (pintype "passive"))
      (node (ref "R5") (pin "2") (pinfunction "2_2") (pintype "passive"))
      (node (ref "R6") (pin "2") (pinfunction "2_2") (pintype "passive"))
    )
    (net (code "51") (name "unconnected-(S1-O-Pad1)") (class "Default")
      (node (ref "S1") (pin "1") (pinfunction "O_1") (pintype "passive"))
    )
    (net (code "52") (name "unconnected-(S2-O-Pad1)") (class "Default")
      (node (ref "S2") (pin "1") (pinfunction "O_1") (pintype "passive"))
    )
    (net (code "53") (name "unconnected-(S3-O-Pad1)") (class "Default")
      (node (ref "S3") (pin "1") (pinfunction "O_1") (pintype "passive"))
    )
    (net (code "54") (name "unconnected-(S4-O-Pad1)") (class "Default")
      (node (ref "S4") (pin "1") (pinfunction "O_1") (pintype "passive"))
    )
    (net (code "55") (name "unconnected-(S5-O-Pad1)") (class "Default")
      (node (ref "S5") (pin "1") (pinfunction "O_1") (pintype "passive"))
    )
    (net (code "56") (name "unconnected-(S6-O-Pad1)") (class "Default")
      (node (ref "S6") (pin "1") (pinfunction "O_1") (pintype "passive"))
    )
    (net (code "57") (name "unconnected-(S7-O-Pad1)") (class "Default")
      (node (ref "S7") (pin "1") (pinfunction "O_1") (pintype "passive"))
    )
    (net (code "58") (name "unconnected-(S8-O-Pad1)") (class "Default")
      (node (ref "S8") (pin "1") (pinfunction "O_1") (pintype "passive"))
    )
    (net (code "59") (name "unconnected-(S9-O-Pad1)") (class "Default")
      (node (ref "S9") (pin "1") (pinfunction "O_1") (pintype "passive"))
    )
    (net (code "60") (name "unconnected-(S10-O-Pad1)") (class "Default")
      (node (ref "S10") (pin "1") (pinfunction "O_1") (pintype "passive"))
    )
    (net (code "61") (name "unconnected-(S11-O-Pad1)") (class "Default")
      (node (ref "S11") (pin "1") (pinfunction "O_1") (pintype "passive"))
    )
    (net (code "62") (name "unconnected-(S12-O-Pad1)") (class "Default")
      (node (ref "S12") (pin "1") (pinfunction "O_1") (pintype "passive"))
    )
    (net (code "63") (name "unconnected-(S13-O-Pad1)") (class "Default")
      (node (ref "S13") (pin "1") (pinfunction "O_1") (pintype "passive"))
    )
    (net (code "64") (name "unconnected-(S14-O-Pad1)") (class "Default")
      (node (ref "S14") (pin "1") (pinfunction "O_1") (pintype "passive"))
    )
    (net (code "65") (name "unconnected-(S19-O-Pad1)") (class "Default")
      (node (ref "S19") (pin "1") (pinfunction "O_1") (pintype "passive"))
    )
    (net (code "66") (name "unconnected-(S20-O-Pad1)") (class "Default")
      (node (ref "S20") (pin "1") (pinfunction "O_1") (pintype "passive"))
    )
  )
)
